# PowerSupply.net
KiCad netlist of a schematic drawn in Altium Designer
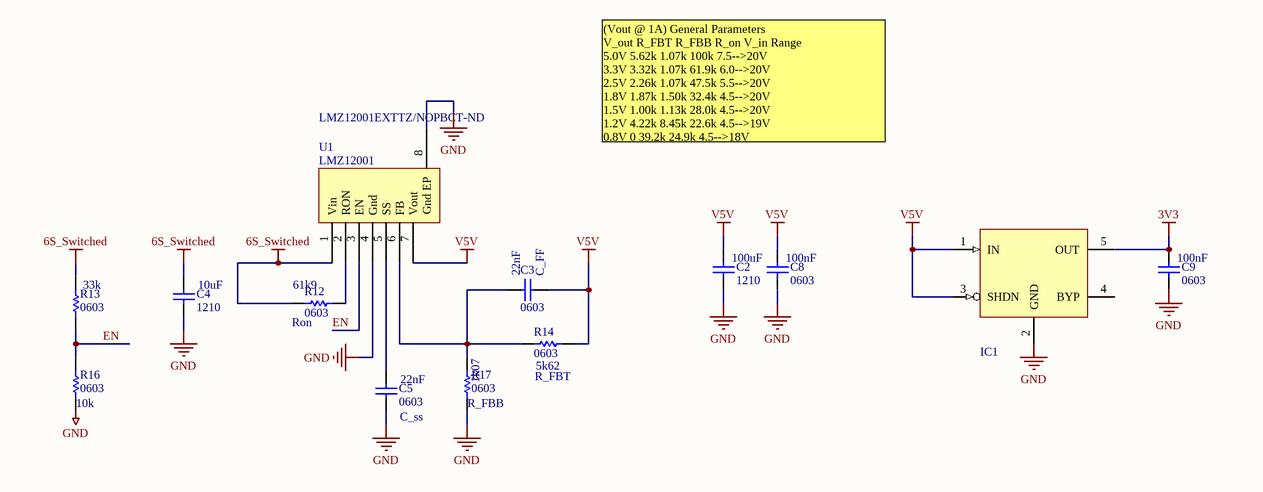
[diagram p0: PowerSupply.SchDoc]

(export (version "E")
  (design (tool "Eeschema 10.0.6"))
  (components
    (comp (ref "C2")
      (value "100uF")
      (footprint "1210_M")
      (description "Default Capacitor")
      (fields (field (name "PACKAGE") "1210") (field (name "Comment") "C"))
      (libsource (lib "UNSW_LIB") (part "C"))
    )
    (comp (ref "C3")
      (value "22nF")
      (footprint "0603_M")
      (description "Default Capacitor")
      (fields (field (name "PACKAGE") "0603") (field (name "Comment") "C"))
      (libsource (lib "UNSW_LIB") (part "C"))
    )
    (comp (ref "C4")
      (value "10uF")
      (footprint "1210_M")
      (description "Default Capacitor")
      (fields (field (name "PACKAGE") "1210") (field (name "Comment") "C"))
      (libsource (lib "UNSW_LIB") (part "C"))
    )
    (comp (ref "C5")
      (value "22nF")
      (footprint "0603_M")
      (description "Default Capacitor")
      (fields (field (name "PACKAGE") "0603") (field (name "Comment") "C"))
      (libsource (lib "UNSW_LIB") (part "C"))
    )
    (comp (ref "C8")
      (value "100nF")
      (footprint "0603_M")
      (description "Default Capacitor")
      (fields (field (name "PACKAGE") "0603") (field (name "Comment") "C"))
      (libsource (lib "UNSW_LIB") (part "C"))
    )
    (comp (ref "C9")
      (value "100nF")
      (footprint "0603_M")
      (description "Default Capacitor")
      (fields (field (name "PACKAGE") "0603") (field (name "Comment") "C"))
      (libsource (lib "UNSW_LIB") (part "C"))
    )
    (comp (ref "IC1")
      (value "3.3V Regulator")
      (footprint "SOT23-5")
      (description "3.3V regulator")
      (fields
        (field (name "MANUFACTURER") "Micrel Inc")
        (field (name "MANUFACTURER PART NUMBER") "MIC5259-3.3YD5 TR")
      )
      (libsource (lib "UNSW_LIB") (part "MIC5259-3.3"))
    )
    (comp (ref "R12")
      (value "61k9")
      (footprint "0603_M")
      (description "Resistor")
      (fields (field (name "PACKAGE") "0603") (field (name "Comment") "R"))
      (libsource (lib "UNSW_LIB") (part "R"))
    )
    (comp (ref "R13")
      (value "33k")
      (footprint "0603_M")
      (description "Resistor")
      (fields (field (name "PACKAGE") "0603") (field (name "Comment") "R"))
      (libsource (lib "UNSW_LIB") (part "R"))
    )
    (comp (ref "R14")
      (value "5k62")
      (footprint "0603_M")
      (description "Resistor")
      (fields (field (name "PACKAGE") "0603") (field (name "Comment") "R"))
      (libsource (lib "UNSW_LIB") (part "R"))
    )
    (comp (ref "R16")
      (value "10k")
      (footprint "0603_M")
      (description "Resistor")
      (fields (field (name "PACKAGE") "0603") (field (name "Comment") "R"))
      (libsource (lib "UNSW_LIB") (part "R"))
    )
    (comp (ref "R17")
      (value "1k07")
      (footprint "0603_M")
      (description "Resistor")
      (fields (field (name "PACKAGE") "0603") (field (name "Comment") "R"))
      (libsource (lib "UNSW_LIB") (part "R"))
    )
    (comp (ref "U1")
      (value "LMZ12001")
      (footprint "LMZ12001")
      (description "Switching Regulator")
      (fields (field (name "SUPPLIER PART NUMBER 1") "LMZ12001EXTTZ/NOPBCT-ND"))
      (libsource (lib "Smart_DCDC") (part "LMZ12001"))
    )
  )
  (nets
    (net (code "1") (name "/EN") (class "Default")
      (node (ref "R13") (pin "1") (pinfunction "1_1") (pintype "passive"))
      (node (ref "R16") (pin "2") (pinfunction "2_2") (pintype "passive"))
      (node (ref "U1") (pin "3") (pinfunction "EN_3") (pintype "passive"))
    )
    (net (code "2") (name "3V3") (class "Default")
      (node (ref "C9") (pin "1") (pinfunction "1_1") (pintype "passive"))
      (node (ref "IC1") (pin "5") (pinfunction "OUT_5") (pintype "power_in"))
    )
    (net (code "3") (name "6S_Switched") (class "Default")
      (node (ref "C4") (pin "1") (pinfunction "1_1") (pintype "passive"))
      (node (ref "R12") (pin "2") (pinfunction "2_2") (pintype "passive"))
      (node (ref "R13") (pin "2") (pinfunction "2_2") (pintype "passive"))
      (node (ref "U1") (pin "1") (pinfunction "Vin_1") (pintype "passive"))
    )
    (net (code "4") (name "GND") (class "Default")
      (node (ref "C2") (pin "2") (pinfunction "2_2") (pintype "passive"))
      (node (ref "C4") (pin "2") (pinfunction "2_2") (pintype "passive"))
      (node (ref "C5") (pin "2") (pinfunction "2_2") (pintype "passive"))
      (node (ref "C8") (pin "2") (pinfunction "2_2") (pintype "passive"))
      (node (ref "C9") (pin "2") (pinfunction "2_2") (pintype "passive"))
      (node (ref "IC1") (pin "2") (pinfunction "GND_2") (pintype "power_in"))
      (node (ref "R16") (pin "1") (pinfunction "1_1") (pintype "passive"))
      (node (ref "R17") (pin "1") (pinfunction "1_1") (pintype "passive"))
      (node (ref "U1") (pin "4") (pinfunction "Gnd_4") (pintype "passive"))
      (node (ref "U1") (pin "8") (pinfunction "Gnd_EP_8") (pintype "passive"))
    )
    (net (code "5") (name "Net-(U1-FB)") (class "Default")
      (node (ref "C3") (pin "1") (pinfunction "1_1") (pintype "passive"))
      (node (ref "R14") (pin "1") (pinfunction "1_1") (pintype "passive"))
      (node (ref "R17") (pin "2") (pinfunction "2_2") (pintype "passive"))
      (node (ref "U1") (pin "6") (pinfunction "FB_6") (pintype "passive"))
    )
    (net (code "6") (name "Net-(U1-RON)") (class "Default")
      (node (ref "R12") (pin "1") (pinfunction "1_1") (pintype "passive"))
      (node (ref "U1") (pin "2") (pinfunction "RON_2") (pintype "passive"))
    )
    (net (code "7") (name "Net-(U1-SS)") (class "Default")
      (node (ref "C5") (pin "1") (pinfunction "1_1") (pintype "passive"))
      (node (ref "U1") (pin "5") (pinfunction "SS_5") (pintype "passive"))
    )
    (net (code "8") (name "V5V") (class "Default")
      (node (ref "C2") (pin "1") (pinfunction "1_1") (pintype "passive"))
      (node (ref "C3") (pin "2") (pinfunction "2_2") (pintype "passive"))
      (node (ref "C8") (pin "1") (pinfunction "1_1") (pintype "passive"))
      (node (ref "IC1") (pin "1") (pinfunction "IN_1") (pintype "input"))
      (node (ref "IC1") (pin "3") (pinfunction "SHDN_3") (pintype "input"))
      (node (ref "R14") (pin "2") (pinfunction "2_2") (pintype "passive"))
      (node (ref "U1") (pin "7") (pinfunction "Vout_7") (pintype "passive"))
    )
    (net (code "9") (name "unconnected-(IC1-BYP-Pad4)") (class "Default")
      (node (ref "IC1") (pin "4") (pinfunction "BYP_4") (pintype "power_in"))
    )
  )
)
